# Sheet2.net
KiCad netlist of a schematic drawn in Altium Designer
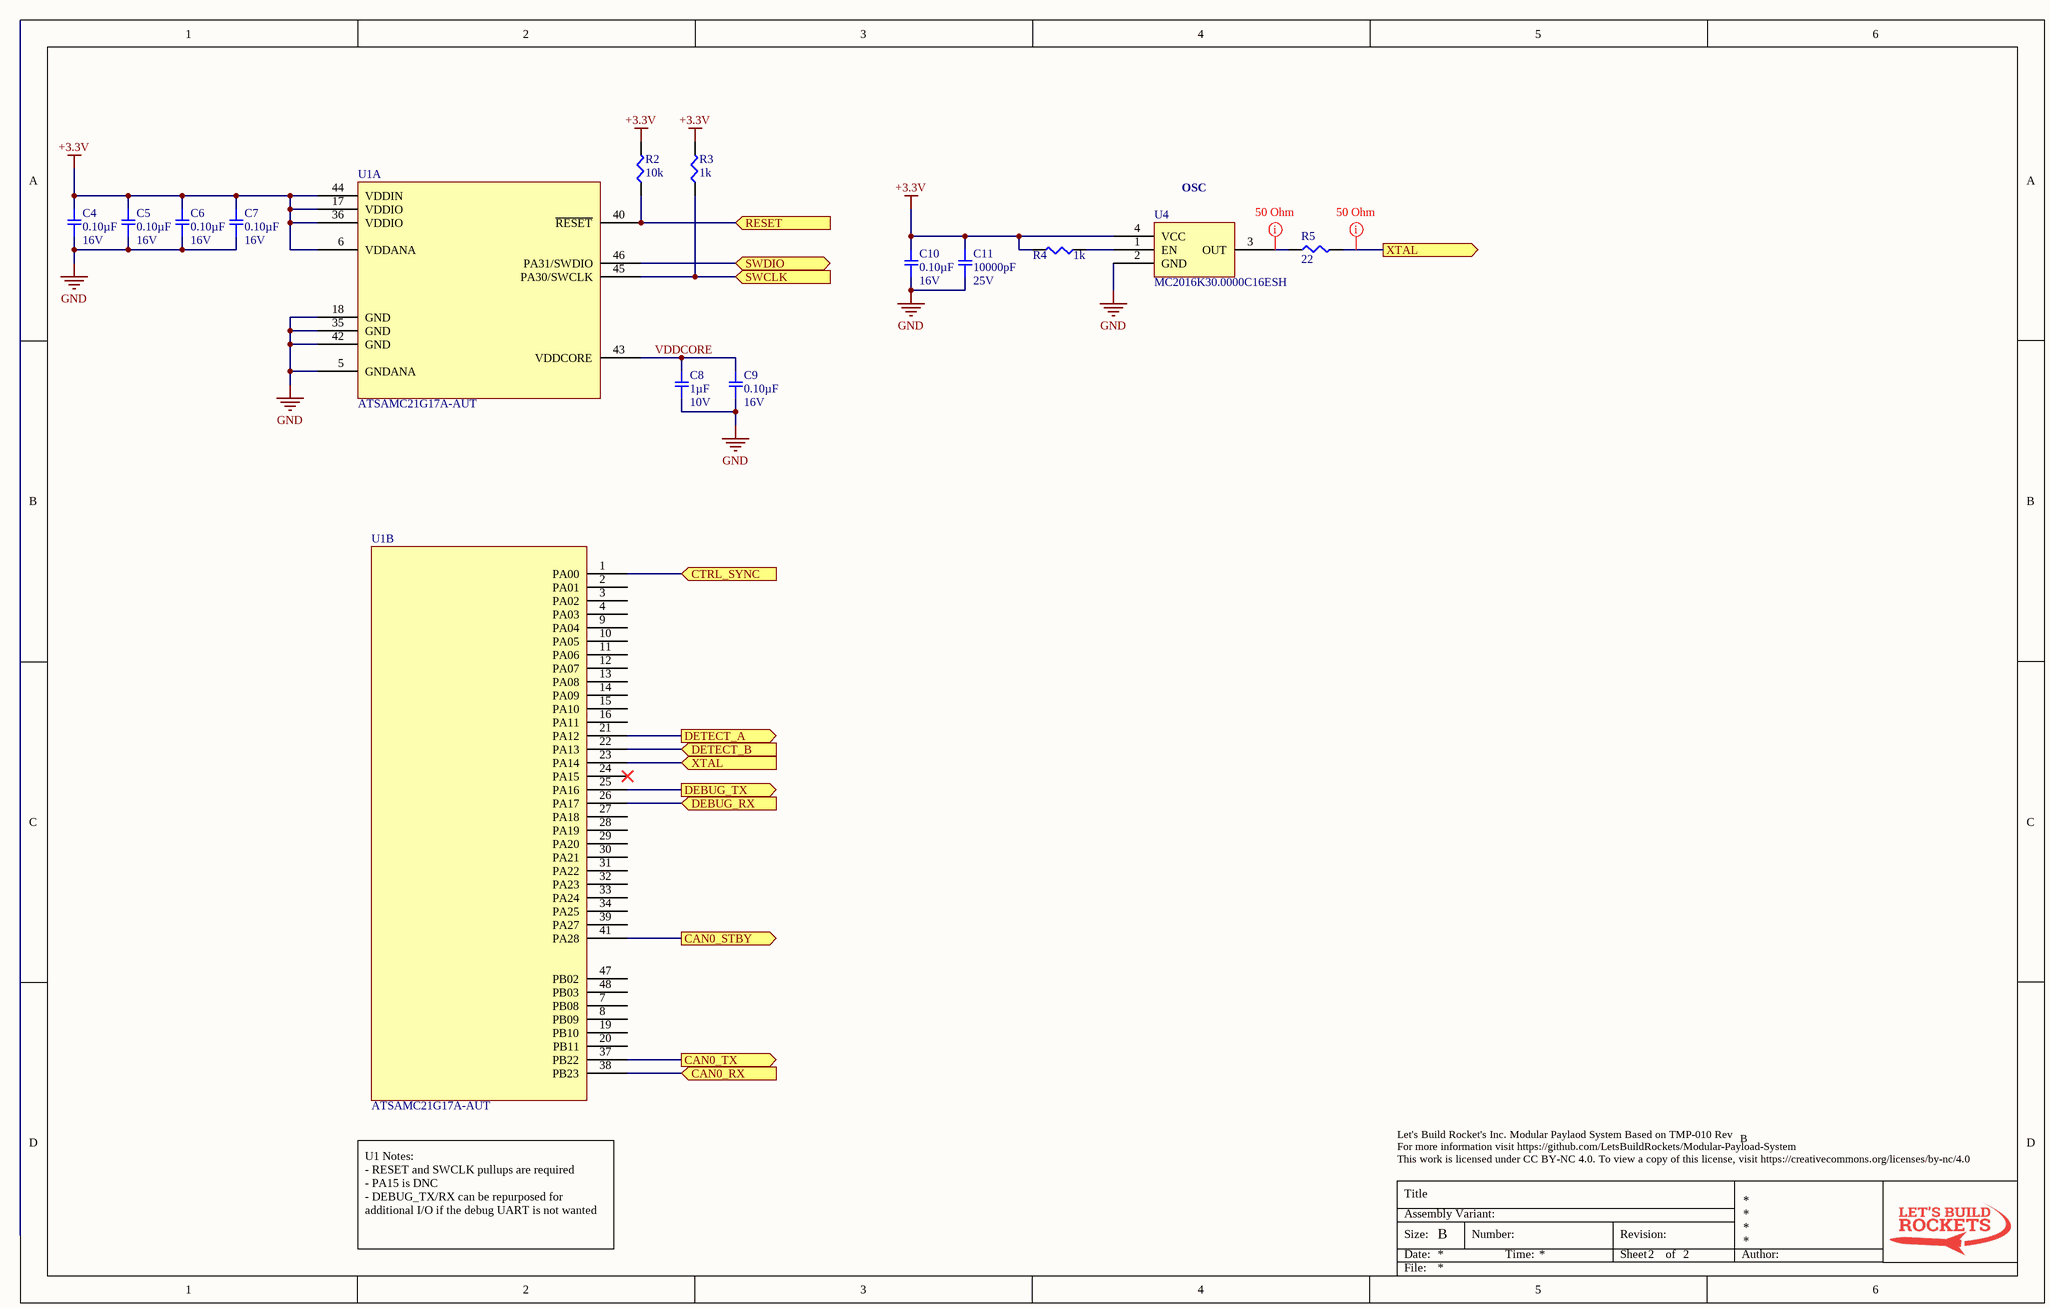
[diagram p0: Sheet2.SchDoc]

(export (version "E")
  (design (tool "Eeschema 10.0.6"))
  (components
    (comp (ref "C4")
      (value "0.10µF")
      (footprint "SMD-0402C")
      (description "CAP CER 0.1UF 16V X7R 0402")
      (fields
        (field (name "DIGI-KEY PART NUMBER") "490-4759-1-ND")
        (field (name "PART NUMBER") "GCM155R71C104KA55D")
        (field (name "VOLTAGE") "16V")
      )
      (libsource (lib "capacitor_murata_0402") (part "GCM155R71C104KA55D"))
    )
    (comp (ref "C5")
      (value "0.10µF")
      (footprint "SMD-0402C")
      (description "CAP CER 0.1UF 16V X7R 0402")
      (fields
        (field (name "DIGI-KEY PART NUMBER") "490-4759-1-ND")
        (field (name "PART NUMBER") "GCM155R71C104KA55D")
        (field (name "VOLTAGE") "16V")
      )
      (libsource (lib "capacitor_murata_0402") (part "GCM155R71C104KA55D"))
    )
    (comp (ref "C6")
      (value "0.10µF")
      (footprint "SMD-0402C")
      (description "CAP CER 0.1UF 16V X7R 0402")
      (fields
        (field (name "DIGI-KEY PART NUMBER") "490-4759-1-ND")
        (field (name "PART NUMBER") "GCM155R71C104KA55D")
        (field (name "VOLTAGE") "16V")
      )
      (libsource (lib "capacitor_murata_0402") (part "GCM155R71C104KA55D"))
    )
    (comp (ref "C7")
      (value "0.10µF")
      (footprint "SMD-0402C")
      (description "CAP CER 0.1UF 16V X7R 0402")
      (fields
        (field (name "DIGI-KEY PART NUMBER") "490-4759-1-ND")
        (field (name "PART NUMBER") "GCM155R71C104KA55D")
        (field (name "VOLTAGE") "16V")
      )
      (libsource (lib "capacitor_murata_0402") (part "GCM155R71C104KA55D"))
    )
    (comp (ref "C8")
      (value "1µF")
      (footprint "SMD-0402C")
      (description "CAP CER 1UF 10V X7S 0402")
      (fields
        (field (name "DIGI-KEY PART NUMBER") "490-13409-1-ND")
        (field (name "PART NUMBER") "GCM155C71A105KE38D")
        (field (name "VOLTAGE") "10V")
      )
      (libsource (lib "capacitor_murata_0402") (part "GCM155C71A105KE38D"))
    )
    (comp (ref "C9")
      (value "0.10µF")
      (footprint "SMD-0402C")
      (description "CAP CER 0.1UF 16V X7R 0402")
      (fields
        (field (name "DIGI-KEY PART NUMBER") "490-4759-1-ND")
        (field (name "PART NUMBER") "GCM155R71C104KA55D")
        (field (name "VOLTAGE") "16V")
      )
      (libsource (lib "capacitor_murata_0402") (part "GCM155R71C104KA55D"))
    )
    (comp (ref "C10")
      (value "0.10µF")
      (footprint "SMD-0402C")
      (description "CAP CER 0.1UF 16V X7R 0402")
      (fields
        (field (name "DIGI-KEY PART NUMBER") "490-4759-1-ND")
        (field (name "PART NUMBER") "GCM155R71C104KA55D")
        (field (name "VOLTAGE") "16V")
      )
      (libsource (lib "capacitor_murata_0402") (part "GCM155R71C104KA55D"))
    )
    (comp (ref "C11")
      (value "10000pF")
      (footprint "SMD-0402C")
      (description "CAP CER 10000PF 25V X7R 0402")
      (fields
        (field (name "DIGI-KEY PART NUMBER") "490-6043-1-ND")
        (field (name "PART NUMBER") "GCM155R71E103KA37D")
        (field (name "VOLTAGE") "25V")
      )
      (libsource (lib "capacitor_murata_0402") (part "GCM155R71E103KA37D"))
    )
    (comp (ref "R2")
      (value "10k")
      (footprint "SMD-0402-RES")
      (description "RES SMD 10K OHM 5% 1/10W 0402")
      (fields (field (name "PART NUMBER") "ERJ-2GEJ103X") (field (name "DIGI-KEY PART NUMBER") "P10KJCT-ND"))
      (libsource (lib "Panasonic_ERJ_0402") (part "ERJ-2GEJ103X"))
    )
    (comp (ref "R3")
      (value "1k")
      (footprint "SMD-0402-RES")
      (description "RES SMD 1K OHM 5% 1/10W 0402")
      (fields (field (name "PART NUMBER") "ERJ-2GEJ102X") (field (name "DIGI-KEY PART NUMBER") "P1.0KJCT-ND"))
      (libsource (lib "Panasonic_ERJ_0402") (part "ERJ-2GEJ102X"))
    )
    (comp (ref "R4")
      (value "1k")
      (footprint "SMD-0402-RES")
      (description "RES SMD 1K OHM 5% 1/10W 0402")
      (fields (field (name "PART NUMBER") "ERJ-2GEJ102X") (field (name "DIGI-KEY PART NUMBER") "P1.0KJCT-ND"))
      (libsource (lib "Panasonic_ERJ_0402") (part "ERJ-2GEJ102X"))
    )
    (comp (ref "R5")
      (value "22")
      (footprint "SMD-0402-RES")
      (description "RES SMD 22 OHM 1% 1/10W 0402")
      (fields
        (field (name "PART NUMBER") "ERJ-2RKF22R0X")
        (field (name "DIGI-KEY PART NUMBER") "P22.0LCT-ND")
      )
      (libsource (lib "Panasonic_ERJ_0402") (part "ERJ-2RKF22R0X"))
    )
    (comp (ref "U1")
      (value "ATSAMC21G17A-AUT")
      (footprint "TSQFP50P900X900X120-48N")
      (libsource (lib "ModularPayload") (part "ATSAMC21G17A-AUT"))
    )
    (comp (ref "U4")
      (value "MC2016K30.0000C16ESH")
      (footprint "MC2016")
      (libsource (lib "ModularPayload") (part "MC2016K30.0000C16ESH"))
    )
  )
  (nets
    (net (code "1") (name "+3.3V") (class "Default")
      (node (ref "C10") (pin "2") (pinfunction "2_2") (pintype "passive"))
      (node (ref "C11") (pin "2") (pinfunction "2_2") (pintype "passive"))
      (node (ref "C4") (pin "2") (pinfunction "2_2") (pintype "passive"))
      (node (ref "C5") (pin "2") (pinfunction "2_2") (pintype "passive"))
      (node (ref "C6") (pin "2") (pinfunction "2_2") (pintype "passive"))
      (node (ref "C7") (pin "2") (pinfunction "2_2") (pintype "passive"))
      (node (ref "R2") (pin "2") (pinfunction "2_2") (pintype "passive"))
      (node (ref "R3") (pin "2") (pinfunction "2_2") (pintype "passive"))
      (node (ref "R4") (pin "2") (pinfunction "2_2") (pintype "passive"))
      (node (ref "U1") (pin "17") (pinfunction "VDDIO_17") (pintype "passive"))
      (node (ref "U1") (pin "36") (pinfunction "VDDIO_36") (pintype "passive"))
      (node (ref "U1") (pin "44") (pinfunction "VDDIN_44") (pintype "passive"))
      (node (ref "U1") (pin "6") (pinfunction "VDDANA_6") (pintype "passive"))
      (node (ref "U4") (pin "4") (pinfunction "VCC_4") (pintype "passive"))
    )
    (net (code "2") (name "/CAN0_RX") (class "Default")
      (node (ref "U1") (pin "38") (pinfunction "PB23_38") (pintype "passive"))
    )
    (net (code "3") (name "/CAN0_STBY") (class "Default")
      (node (ref "U1") (pin "41") (pinfunction "PA28_41") (pintype "passive"))
    )
    (net (code "4") (name "/CAN0_TX") (class "Default")
      (node (ref "U1") (pin "37") (pinfunction "PB22_37") (pintype "passive"))
    )
    (net (code "5") (name "/CTRL_SYNC") (class "Default")
      (node (ref "U1") (pin "1") (pinfunction "PA00_1") (pintype "passive"))
    )
    (net (code "6") (name "/DEBUG_RX") (class "Default")
      (node (ref "U1") (pin "26") (pinfunction "PA17_26") (pintype "passive"))
    )
    (net (code "7") (name "/DEBUG_TX") (class "Default")
      (node (ref "U1") (pin "25") (pinfunction "PA16_25") (pintype "passive"))
    )
    (net (code "8") (name "/DETECT_A") (class "Default")
      (node (ref "U1") (pin "21") (pinfunction "PA12_21") (pintype "passive"))
    )
    (net (code "9") (name "/DETECT_B") (class "Default")
      (node (ref "U1") (pin "22") (pinfunction "PA13_22") (pintype "passive"))
    )
    (net (code "10") (name "/RESET") (class "Default")
      (node (ref "R2") (pin "1") (pinfunction "1_1") (pintype "passive"))
      (node (ref "U1") (pin "40") (pinfunction "~{RESET}_40") (pintype "passive"))
    )
    (net (code "11") (name "/SWCLK") (class "Default")
      (node (ref "R3") (pin "1") (pinfunction "1_1") (pintype "passive"))
      (node (ref "U1") (pin "45") (pinfunction "PA30/SWCLK_45") (pintype "passive"))
    )
    (net (code "12") (name "/SWDIO") (class "Default")
      (node (ref "U1") (pin "46") (pinfunction "PA31/SWDIO_46") (pintype "passive"))
    )
    (net (code "13") (name "/VDDCORE") (class "Default")
      (node (ref "C8") (pin "2") (pinfunction "2_2") (pintype "passive"))
      (node (ref "C9") (pin "2") (pinfunction "2_2") (pintype "passive"))
      (node (ref "U1") (pin "43") (pinfunction "VDDCORE_43") (pintype "passive"))
    )
    (net (code "14") (name "/XTAL") (class "Default")
      (node (ref "R5") (pin "2") (pinfunction "2_2") (pintype "passive"))
      (node (ref "U1") (pin "23") (pinfunction "PA14_23") (pintype "passive"))
    )
    (net (code "15") (name "GND") (class "Default")
      (node (ref "C10") (pin "1") (pinfunction "1_1") (pintype "passive"))
      (node (ref "C11") (pin "1") (pinfunction "1_1") (pintype "passive"))
      (node (ref "C4") (pin "1") (pinfunction "1_1") (pintype "passive"))
      (node (ref "C5") (pin "1") (pinfunction "1_1") (pintype "passive"))
      (node (ref "C6") (pin "1") (pinfunction "1_1") (pintype "passive"))
      (node (ref "C7") (pin "1") (pinfunction "1_1") (pintype "passive"))
      (node (ref "C8") (pin "1") (pinfunction "1_1") (pintype "passive"))
      (node (ref "C9") (pin "1") (pinfunction "1_1") (pintype "passive"))
      (node (ref "U1") (pin "18") (pinfunction "GND_18") (pintype "passive"))
      (node (ref "U1") (pin "35") (pinfunction "GND_35") (pintype "passive"))
      (node (ref "U1") (pin "42") (pinfunction "GND_42") (pintype "passive"))
      (node (ref "U1") (pin "5") (pinfunction "GNDANA_5") (pintype "passive"))
      (node (ref "U4") (pin "2") (pinfunction "GND_2") (pintype "passive"))
    )
    (net (code "16") (name "Net-(U4-EN)") (class "Default")
      (node (ref "R4") (pin "1") (pinfunction "1_1") (pintype "passive"))
      (node (ref "U4") (pin "1") (pinfunction "EN_1") (pintype "passive"))
    )
    (net (code "17") (name "Net-(U4-OUT)") (class "Default")
      (node (ref "R5") (pin "1") (pinfunction "1_1") (pintype "passive"))
      (node (ref "U4") (pin "3") (pinfunction "OUT_3") (pintype "passive"))
    )
    (net (code "18") (name "unconnected-(U1B-PA01-Pad2)") (class "Default")
      (node (ref "U1") (pin "2") (pinfunction "PA01_2") (pintype "passive"))
    )
    (net (code "19") (name "unconnected-(U1B-PA02-Pad3)") (class "Default")
      (node (ref "U1") (pin "3") (pinfunction "PA02_3") (pintype "passive"))
    )
    (net (code "20") (name "unconnected-(U1B-PA03-Pad4)") (class "Default")
      (node (ref "U1") (pin "4") (pinfunction "PA03_4") (pintype "passive"))
    )
    (net (code "21") (name "unconnected-(U1B-PA04-Pad9)") (class "Default")
      (node (ref "U1") (pin "9") (pinfunction "PA04_9") (pintype "passive"))
    )
    (net (code "22") (name "unconnected-(U1B-PA05-Pad10)") (class "Default")
      (node (ref "U1") (pin "10") (pinfunction "PA05_10") (pintype "passive"))
    )
    (net (code "23") (name "unconnected-(U1B-PA06-Pad11)") (class "Default")
      (node (ref "U1") (pin "11") (pinfunction "PA06_11") (pintype "passive"))
    )
    (net (code "24") (name "unconnected-(U1B-PA07-Pad12)") (class "Default")
      (node (ref "U1") (pin "12") (pinfunction "PA07_12") (pintype "passive"))
    )
    (net (code "25") (name "unconnected-(U1B-PA08-Pad13)") (class "Default")
      (node (ref "U1") (pin "13") (pinfunction "PA08_13") (pintype "passive"))
    )
    (net (code "26") (name "unconnected-(U1B-PA09-Pad14)") (class "Default")
      (node (ref "U1") (pin "14") (pinfunction "PA09_14") (pintype "passive"))
    )
    (net (code "27") (name "unconnected-(U1B-PA10-Pad15)") (class "Default")
      (node (ref "U1") (pin "15") (pinfunction "PA10_15") (pintype "passive"))
    )
    (net (code "28") (name "unconnected-(U1B-PA11-Pad16)") (class "Default")
      (node (ref "U1") (pin "16") (pinfunction "PA11_16") (pintype "passive"))
    )
    (net (code "29") (name "unconnected-(U1B-PA15-Pad24)") (class "Default")
      (node (ref "U1") (pin "24") (pinfunction "PA15_24") (pintype "passive+no_connect"))
    )
    (net (code "30") (name "unconnected-(U1B-PA18-Pad27)") (class "Default")
      (node (ref "U1") (pin "27") (pinfunction "PA18_27") (pintype "passive"))
    )
    (net (code "31") (name "unconnected-(U1B-PA19-Pad28)") (class "Default")
      (node (ref "U1") (pin "28") (pinfunction "PA19_28") (pintype "passive"))
    )
    (net (code "32") (name "unconnected-(U1B-PA20-Pad29)") (class "Default")
      (node (ref "U1") (pin "29") (pinfunction "PA20_29") (pintype "passive"))
    )
    (net (code "33") (name "unconnected-(U1B-PA21-Pad30)") (class "Default")
      (node (ref "U1") (pin "30") (pinfunction "PA21_30") (pintype "passive"))
    )
    (net (code "34") (name "unconnected-(U1B-PA22-Pad31)") (class "Default")
      (node (ref "U1") (pin "31") (pinfunction "PA22_31") (pintype "passive"))
    )
    (net (code "35") (name "unconnected-(U1B-PA23-Pad32)") (class "Default")
      (node (ref "U1") (pin "32") (pinfunction "PA23_32") (pintype "passive"))
    )
    (net (code "36") (name "unconnected-(U1B-PA24-Pad33)") (class "Default")
      (node (ref "U1") (pin "33") (pinfunction "PA24_33") (pintype "passive"))
    )
    (net (code "37") (name "unconnected-(U1B-PA25-Pad34)") (class "Default")
      (node (ref "U1") (pin "34") (pinfunction "PA25_34") (pintype "passive"))
    )
    (net (code "38") (name "unconnected-(U1B-PA27-Pad39)") (class "Default")
      (node (ref "U1") (pin "39") (pinfunction "PA27_39") (pintype "passive"))
    )
    (net (code "39") (name "unconnected-(U1B-PB02-Pad47)") (class "Default")
      (node (ref "U1") (pin "47") (pinfunction "PB02_47") (pintype "passive"))
    )
    (net (code "40") (name "unconnected-(U1B-PB03-Pad48)") (class "Default")
      (node (ref "U1") (pin "48") (pinfunction "PB03_48") (pintype "passive"))
    )
    (net (code "41") (name "unconnected-(U1B-PB08-Pad7)") (class "Default")
      (node (ref "U1") (pin "7") (pinfunction "PB08_7") (pintype "passive"))
    )
    (net (code "42") (name "unconnected-(U1B-PB09-Pad8)") (class "Default")
      (node (ref "U1") (pin "8") (pinfunction "PB09_8") (pintype "passive"))
    )
    (net (code "43") (name "unconnected-(U1B-PB10-Pad19)") (class "Default")
      (node (ref "U1") (pin "19") (pinfunction "PB10_19") (pintype "passive"))
    )
    (net (code "44") (name "unconnected-(U1B-PB11-Pad20)") (class "Default")
      (node (ref "U1") (pin "20") (pinfunction "PB11_20") (pintype "passive"))
    )
  )
)
